# Controller.net
KiCad netlist of a schematic drawn in EAGLE
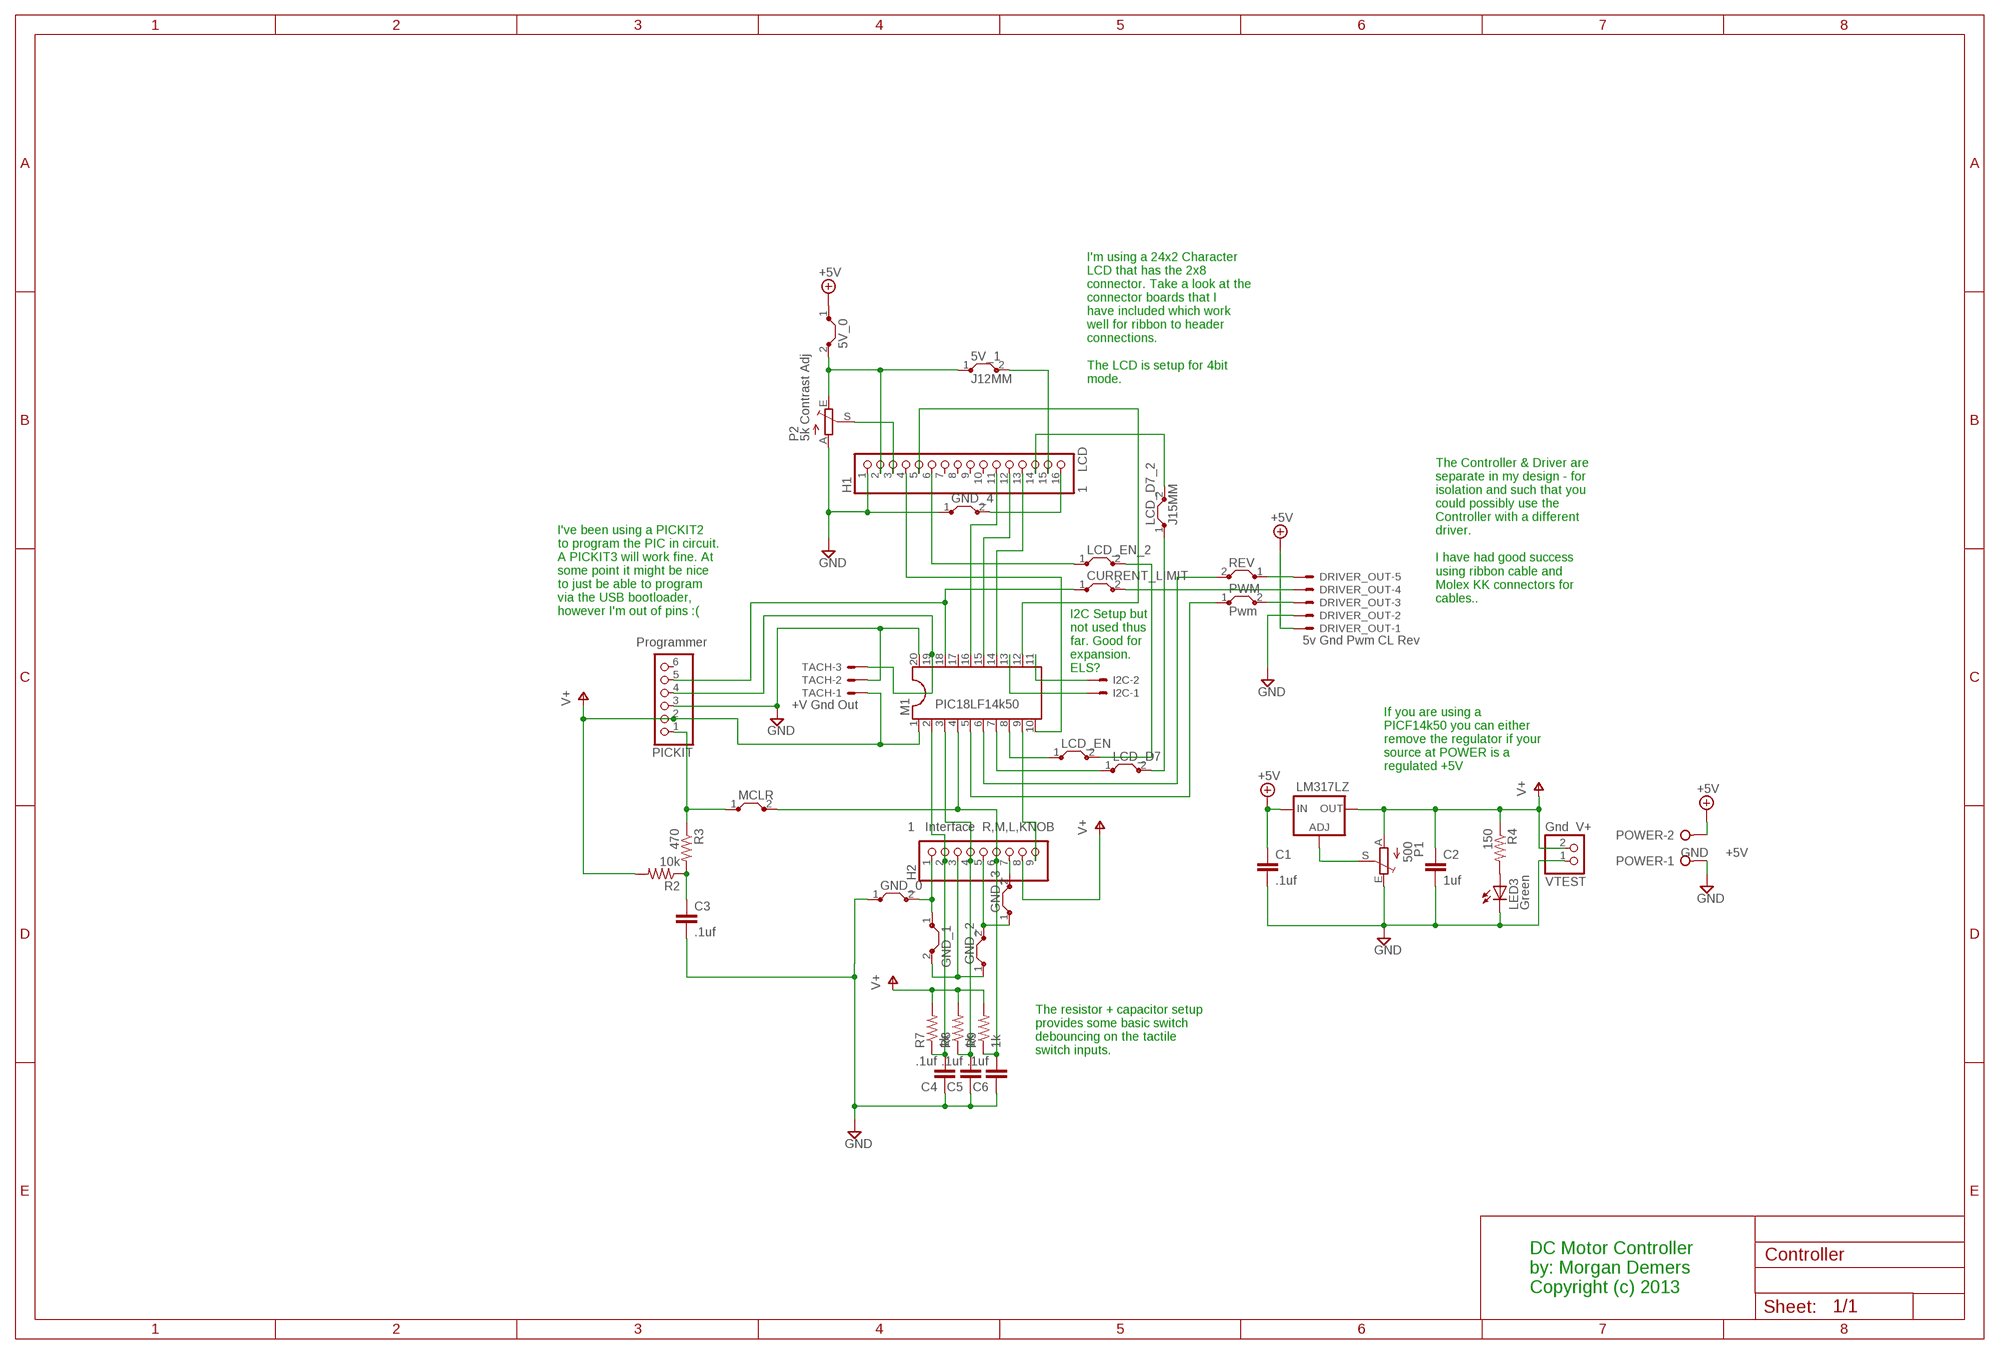
[diagram p0: schematic, sheet 1]

(export (version "E")
  (design (tool "Eeschema 10.0.6"))
  (components
    (comp (ref "5V_0")
      (value "J5MM")
      (footprint "eagle-import:05")
      (libsource (lib "eagle-import") (part "J5MM"))
    )
    (comp (ref "5V_1")
      (value "J12MM")
      (footprint "eagle-import:12")
      (libsource (lib "eagle-import") (part "J12MM"))
    )
    (comp (ref "C1")
      (value ".1uf")
      (footprint "eagle-import:C2.5-3")
      (libsource (lib "eagle-import") (part "C2,5-3"))
    )
    (comp (ref "C2")
      (value "1uf")
      (footprint "eagle-import:C2.5-3")
      (libsource (lib "eagle-import") (part "C2,5-3"))
    )
    (comp (ref "C3")
      (value ".1uf")
      (footprint "eagle-import:C2.5-3")
      (libsource (lib "eagle-import") (part "C2,5-3"))
    )
    (comp (ref "C4")
      (value ".1uf")
      (footprint "eagle-import:C5B2.5")
      (libsource (lib "eagle-import") (part "C5/2.5"))
    )
    (comp (ref "C5")
      (value ".1uf")
      (footprint "eagle-import:C5B2.5")
      (libsource (lib "eagle-import") (part "C5/2.5"))
    )
    (comp (ref "C6")
      (value ".1uf")
      (footprint "eagle-import:C5B2.5")
      (libsource (lib "eagle-import") (part "C5/2.5"))
    )
    (comp (ref "CURRENT_LIMIT")
      (value "J30MM")
      (footprint "eagle-import:30")
      (libsource (lib "eagle-import") (part "J30MM"))
    )
    (comp (ref "DRIVER_OUT")
      (value "5v Gnd Pwm CL Rev")
      (footprint "eagle-import:22-23-2051")
      (fields (field (name "MF") "MOLEX") (field (name "MPN") "22-23-2051"))
      (libsource (lib "eagle-import") (part "22-23-2051"))
    )
    (comp (ref "GND_0")
      (value "J10MM")
      (footprint "eagle-import:10")
      (libsource (lib "eagle-import") (part "J10MM"))
    )
    (comp (ref "GND_1")
      (value "J5MM")
      (footprint "eagle-import:05")
      (libsource (lib "eagle-import") (part "J5MM"))
    )
    (comp (ref "GND_2")
      (value "J5MM")
      (footprint "eagle-import:05")
      (libsource (lib "eagle-import") (part "J5MM"))
    )
    (comp (ref "GND_3")
      (value "J5MM")
      (footprint "eagle-import:05")
      (libsource (lib "eagle-import") (part "J5MM"))
    )
    (comp (ref "GND_4")
      (value "J10MM")
      (footprint "eagle-import:10")
      (libsource (lib "eagle-import") (part "J10MM"))
    )
    (comp (ref "H1")
      (value "1 LCD")
      (footprint "eagle-import:1X16")
      (libsource (lib "eagle-import") (part "PINHD-1X16"))
    )
    (comp (ref "H2")
      (value "1 Interface R,M,L,KNOB")
      (footprint "eagle-import:1X09")
      (libsource (lib "eagle-import") (part "PINHD-1X9"))
    )
    (comp (ref "I2C")
      (value "22-23-2021")
      (footprint "eagle-import:22-23-2021")
      (fields (field (name "MF") "MOLEX"))
      (libsource (lib "eagle-import") (part "22-23-2021"))
    )
    (comp (ref "LCD_D7")
      (value "J7MM")
      (footprint "eagle-import:07")
      (libsource (lib "eagle-import") (part "J7MM"))
    )
    (comp (ref "LCD_D7_2")
      (value "J15MM")
      (footprint "eagle-import:15")
      (libsource (lib "eagle-import") (part "J15MM"))
    )
    (comp (ref "LCD_EN")
      (value "J7MM")
      (footprint "eagle-import:07")
      (libsource (lib "eagle-import") (part "J7MM"))
    )
    (comp (ref "LCD_EN_2")
      (value "J7MM")
      (footprint "eagle-import:07")
      (libsource (lib "eagle-import") (part "J7MM"))
    )
    (comp (ref "LED3")
      (value "Green")
      (footprint "eagle-import:LSU260")
      (libsource (lib "eagle-import") (part "LEDLSU260"))
    )
    (comp (ref "LM317LZ")
      (value "LM317L")
      (footprint "eagle-import:317L")
      (libsource (lib "eagle-import") (part "LM317L"))
    )
    (comp (ref "M1")
      (value "PIC18LF14k50")
      (footprint "eagle-import:DIL20")
      (libsource (lib "eagle-import") (part "DIL20"))
    )
    (comp (ref "MCLR")
      (value "J15MM")
      (footprint "eagle-import:15")
      (libsource (lib "eagle-import") (part "J15MM"))
    )
    (comp (ref "P1")
      (value "500")
      (footprint "eagle-import:B25P")
      (libsource (lib "eagle-import") (part "TRIM_EU-B25P"))
    )
    (comp (ref "P2")
      (value "5k Contrast Adj")
      (footprint "eagle-import:B25P")
      (libsource (lib "eagle-import") (part "TRIM_EU-B25P"))
    )
    (comp (ref "PICKIT")
      (value "Programmer")
      (footprint "eagle-import:1X06_90")
      (libsource (lib "eagle-import") (part "PINHD-1X6/90"))
    )
    (comp (ref "POWER")
      (value "GND +5V")
      (footprint "eagle-import:W237-132")
      (libsource (lib "eagle-import") (part "W237-02P"))
    )
    (comp (ref "PWM")
      (value "Pwm")
      (footprint "eagle-import:07")
      (libsource (lib "eagle-import") (part "J7MM"))
    )
    (comp (ref "R2")
      (value "10k")
      (footprint "eagle-import:0204V")
      (libsource (lib "eagle-import") (part "R-US_0204/2V"))
    )
    (comp (ref "R3")
      (value "470")
      (footprint "eagle-import:0204V")
      (libsource (lib "eagle-import") (part "R-US_0204/2V"))
    )
    (comp (ref "R4")
      (value "150")
      (footprint "eagle-import:0204V")
      (libsource (lib "eagle-import") (part "R-US_0204/2V"))
    )
    (comp (ref "R7")
      (value "1k")
      (footprint "eagle-import:0204V")
      (libsource (lib "eagle-import") (part "R-US_0204/2V"))
    )
    (comp (ref "R8")
      (value "1k")
      (footprint "eagle-import:0204V")
      (libsource (lib "eagle-import") (part "R-US_0204/2V"))
    )
    (comp (ref "R9")
      (value "1k")
      (footprint "eagle-import:0204V")
      (libsource (lib "eagle-import") (part "R-US_0204/2V"))
    )
    (comp (ref "REV")
      (value "J10MM")
      (footprint "eagle-import:10")
      (libsource (lib "eagle-import") (part "J10MM"))
    )
    (comp (ref "TACH")
      (value "+V Gnd Out")
      (footprint "eagle-import:22-23-2031")
      (fields (field (name "MF") "MOLEX") (field (name "MPN") "22-23-2031"))
      (libsource (lib "eagle-import") (part "22-23-2031"))
    )
    (comp (ref "VTEST")
      (value "Gnd V+")
      (footprint "eagle-import:1X02")
      (libsource (lib "eagle-import") (part "PINHD-1X2"))
    )
  )
  (nets
    (net (code "1") (name "+5V") (class "Default")
      (node (ref "5V_0") (pin "1") (pinfunction "1_1") (pintype "passive"))
      (node (ref "C1") (pin "1") (pinfunction "1_1") (pintype "passive"))
      (node (ref "DRIVER_OUT") (pin "1") (pinfunction "S_1") (pintype "passive"))
      (node (ref "LM317LZ") (pin "3") (pinfunction "IN_3") (pintype "input"))
      (node (ref "POWER") (pin "2") (pinfunction "KL_2") (pintype "passive"))
    )
    (net (code "2") (name "GND") (class "Default")
      (node (ref "C1") (pin "2") (pinfunction "2_2") (pintype "passive"))
      (node (ref "C2") (pin "2") (pinfunction "2_2") (pintype "passive"))
      (node (ref "C3") (pin "2") (pinfunction "2_2") (pintype "passive"))
      (node (ref "C4") (pin "1") (pinfunction "1_1") (pintype "passive"))
      (node (ref "C5") (pin "1") (pinfunction "1_1") (pintype "passive"))
      (node (ref "C6") (pin "1") (pinfunction "1_1") (pintype "passive"))
      (node (ref "DRIVER_OUT") (pin "2") (pinfunction "S_2") (pintype "passive"))
      (node (ref "GND_0") (pin "1") (pinfunction "1_1") (pintype "passive"))
      (node (ref "GND_4") (pin "1") (pinfunction "1_1") (pintype "passive"))
      (node (ref "H1") (pin "1") (pinfunction "1_1") (pintype "passive"))
      (node (ref "LED3") (pin "K") (pinfunction "C_K") (pintype "passive"))
      (node (ref "M1") (pin "20") (pinfunction "20_20") (pintype "passive"))
      (node (ref "P1") (pin "E") (pinfunction "E_E") (pintype "passive"))
      (node (ref "P2") (pin "A") (pinfunction "A_A") (pintype "passive"))
      (node (ref "PICKIT") (pin "3") (pinfunction "3_3") (pintype "passive"))
      (node (ref "POWER") (pin "1") (pinfunction "KL_1") (pintype "passive"))
      (node (ref "TACH") (pin "2") (pinfunction "S_2") (pintype "passive"))
      (node (ref "VTEST") (pin "1") (pinfunction "1_1") (pintype "passive"))
    )
    (net (code "3") (name "Net-(5V_0-Pad2)") (class "Default")
      (node (ref "5V_0") (pin "2") (pinfunction "2_2") (pintype "passive"))
      (node (ref "5V_1") (pin "1") (pinfunction "1_1") (pintype "passive"))
      (node (ref "H1") (pin "2") (pinfunction "2_2") (pintype "passive"))
      (node (ref "P2") (pin "E") (pinfunction "E_E") (pintype "passive"))
    )
    (net (code "4") (name "Net-(5V_1-Pad2)") (class "Default")
      (node (ref "5V_1") (pin "2") (pinfunction "2_2") (pintype "passive"))
      (node (ref "H1") (pin "15") (pinfunction "15_15") (pintype "passive"))
    )
    (net (code "5") (name "Net-(C3-Pad1)") (class "Default")
      (node (ref "C3") (pin "1") (pinfunction "1_1") (pintype "passive"))
      (node (ref "R2") (pin "1") (pinfunction "1_1") (pintype "passive"))
      (node (ref "R3") (pin "2") (pinfunction "2_2") (pintype "passive"))
    )
    (net (code "6") (name "Net-(C4-Pad2)") (class "Default")
      (node (ref "C4") (pin "2") (pinfunction "2_2") (pintype "passive"))
      (node (ref "H2") (pin "2") (pinfunction "2_2") (pintype "passive"))
      (node (ref "M1") (pin "2") (pinfunction "2_2") (pintype "passive"))
      (node (ref "R7") (pin "1") (pinfunction "1_1") (pintype "passive"))
    )
    (net (code "7") (name "Net-(C5-Pad2)") (class "Default")
      (node (ref "C5") (pin "2") (pinfunction "2_2") (pintype "passive"))
      (node (ref "H2") (pin "4") (pinfunction "4_4") (pintype "passive"))
      (node (ref "M1") (pin "3") (pinfunction "3_3") (pintype "passive"))
      (node (ref "R8") (pin "1") (pinfunction "1_1") (pintype "passive"))
    )
    (net (code "8") (name "Net-(C6-Pad2)") (class "Default")
      (node (ref "C6") (pin "2") (pinfunction "2_2") (pintype "passive"))
      (node (ref "H2") (pin "6") (pinfunction "6_6") (pintype "passive"))
      (node (ref "M1") (pin "4") (pinfunction "4_4") (pintype "passive"))
      (node (ref "MCLR") (pin "2") (pinfunction "2_2") (pintype "passive"))
      (node (ref "R9") (pin "1") (pinfunction "1_1") (pintype "passive"))
    )
    (net (code "9") (name "Net-(CURRENT_LIMIT-Pad1)") (class "Default")
      (node (ref "CURRENT_LIMIT") (pin "1") (pinfunction "1_1") (pintype "passive"))
      (node (ref "M1") (pin "18") (pinfunction "18_18") (pintype "passive"))
      (node (ref "PICKIT") (pin "5") (pinfunction "5_5") (pintype "passive"))
    )
    (net (code "10") (name "Net-(DRIVER_OUTC-S)") (class "Default")
      (node (ref "DRIVER_OUT") (pin "3") (pinfunction "S_3") (pintype "passive"))
      (node (ref "PWM") (pin "2") (pinfunction "2_2") (pintype "passive"))
    )
    (net (code "11") (name "Net-(DRIVER_OUTD-S)") (class "Default")
      (node (ref "CURRENT_LIMIT") (pin "2") (pinfunction "2_2") (pintype "passive"))
      (node (ref "DRIVER_OUT") (pin "4") (pinfunction "S_4") (pintype "passive"))
    )
    (net (code "12") (name "Net-(DRIVER_OUTE-S)") (class "Default")
      (node (ref "DRIVER_OUT") (pin "5") (pinfunction "S_5") (pintype "passive"))
      (node (ref "REV") (pin "1") (pinfunction "1_1") (pintype "passive"))
    )
    (net (code "13") (name "Net-(GND_0-Pad2)") (class "Default")
      (node (ref "GND_0") (pin "2") (pinfunction "2_2") (pintype "passive"))
      (node (ref "GND_1") (pin "1") (pinfunction "1_1") (pintype "passive"))
      (node (ref "H2") (pin "1") (pinfunction "1_1") (pintype "passive"))
    )
    (net (code "14") (name "Net-(GND_1-Pad2)") (class "Default")
      (node (ref "GND_1") (pin "2") (pinfunction "2_2") (pintype "passive"))
      (node (ref "GND_2") (pin "1") (pinfunction "1_1") (pintype "passive"))
      (node (ref "H2") (pin "3") (pinfunction "3_3") (pintype "passive"))
    )
    (net (code "15") (name "Net-(GND_2-Pad2)") (class "Default")
      (node (ref "GND_2") (pin "2") (pinfunction "2_2") (pintype "passive"))
      (node (ref "GND_3") (pin "1") (pinfunction "1_1") (pintype "passive"))
      (node (ref "H2") (pin "5") (pinfunction "5_5") (pintype "passive"))
    )
    (net (code "16") (name "Net-(GND_3-Pad2)") (class "Default")
      (node (ref "GND_3") (pin "2") (pinfunction "2_2") (pintype "passive"))
      (node (ref "H2") (pin "7") (pinfunction "7_7") (pintype "passive"))
    )
    (net (code "17") (name "Net-(GND_4-Pad2)") (class "Default")
      (node (ref "GND_4") (pin "2") (pinfunction "2_2") (pintype "passive"))
      (node (ref "H1") (pin "16") (pinfunction "16_16") (pintype "passive"))
    )
    (net (code "18") (name "Net-(H1-Pad3)") (class "Default")
      (node (ref "H1") (pin "3") (pinfunction "3_3") (pintype "passive"))
      (node (ref "P2") (pin "S") (pinfunction "S_S") (pintype "passive"))
    )
    (net (code "19") (name "Net-(H1-Pad4)") (class "Default")
      (node (ref "H1") (pin "4") (pinfunction "4_4") (pintype "passive"))
      (node (ref "M1") (pin "10") (pinfunction "10_10") (pintype "passive"))
    )
    (net (code "20") (name "Net-(H1-Pad5)") (class "Default")
      (node (ref "H1") (pin "5") (pinfunction "5_5") (pintype "passive"))
      (node (ref "M1") (pin "12") (pinfunction "12_12") (pintype "passive"))
    )
    (net (code "21") (name "Net-(H1-Pad6)") (class "Default")
      (node (ref "H1") (pin "6") (pinfunction "6_6") (pintype "passive"))
      (node (ref "LCD_EN_2") (pin "1") (pinfunction "1_1") (pintype "passive"))
    )
    (net (code "22") (name "Net-(H1-Pad11)") (class "Default")
      (node (ref "H1") (pin "11") (pinfunction "11_11") (pintype "passive"))
      (node (ref "M1") (pin "16") (pinfunction "16_16") (pintype "passive"))
    )
    (net (code "23") (name "Net-(H1-Pad12)") (class "Default")
      (node (ref "H1") (pin "12") (pinfunction "12_12") (pintype "passive"))
      (node (ref "M1") (pin "15") (pinfunction "15_15") (pintype "passive"))
    )
    (net (code "24") (name "Net-(H1-Pad13)") (class "Default")
      (node (ref "H1") (pin "13") (pinfunction "13_13") (pintype "passive"))
      (node (ref "M1") (pin "14") (pinfunction "14_14") (pintype "passive"))
    )
    (net (code "25") (name "Net-(H1-Pad14)") (class "Default")
      (node (ref "H1") (pin "14") (pinfunction "14_14") (pintype "passive"))
      (node (ref "LCD_D7_2") (pin "2") (pinfunction "2_2") (pintype "passive"))
    )
    (net (code "26") (name "Net-(H2-Pad9)") (class "Default")
      (node (ref "H2") (pin "9") (pinfunction "9_9") (pintype "passive"))
      (node (ref "M1") (pin "9") (pinfunction "9_9") (pintype "passive"))
    )
    (net (code "27") (name "Net-(I2CA-S)") (class "Default")
      (node (ref "I2C") (pin "1") (pinfunction "S_1") (pintype "passive"))
      (node (ref "M1") (pin "13") (pinfunction "13_13") (pintype "passive"))
    )
    (net (code "28") (name "Net-(I2CB-S)") (class "Default")
      (node (ref "I2C") (pin "2") (pinfunction "S_2") (pintype "passive"))
      (node (ref "M1") (pin "11") (pinfunction "11_11") (pintype "passive"))
    )
    (net (code "29") (name "Net-(LCD_D7-Pad1)") (class "Default")
      (node (ref "LCD_D7") (pin "1") (pinfunction "1_1") (pintype "passive"))
      (node (ref "M1") (pin "7") (pinfunction "7_7") (pintype "passive"))
    )
    (net (code "30") (name "Net-(LCD_D7-Pad2)") (class "Default")
      (node (ref "LCD_D7") (pin "2") (pinfunction "2_2") (pintype "passive"))
      (node (ref "LCD_D7_2") (pin "1") (pinfunction "1_1") (pintype "passive"))
    )
    (net (code "31") (name "Net-(LCD_EN-Pad1)") (class "Default")
      (node (ref "LCD_EN") (pin "1") (pinfunction "1_1") (pintype "passive"))
      (node (ref "M1") (pin "8") (pinfunction "8_8") (pintype "passive"))
    )
    (net (code "32") (name "Net-(LCD_EN-Pad2)") (class "Default")
      (node (ref "LCD_EN") (pin "2") (pinfunction "2_2") (pintype "passive"))
      (node (ref "LCD_EN_2") (pin "2") (pinfunction "2_2") (pintype "passive"))
    )
    (net (code "33") (name "Net-(LED3-PadA)") (class "Default")
      (node (ref "LED3") (pin "A") (pinfunction "A_A") (pintype "passive"))
      (node (ref "R4") (pin "2") (pinfunction "2_2") (pintype "passive"))
    )
    (net (code "34") (name "Net-(LM317LZ-ADJ)") (class "Default")
      (node (ref "LM317LZ") (pin "1") (pinfunction "ADJ_1") (pintype "input"))
      (node (ref "P1") (pin "S") (pinfunction "S_S") (pintype "passive"))
    )
    (net (code "35") (name "Net-(M1-Pad5)") (class "Default")
      (node (ref "M1") (pin "5") (pinfunction "5_5") (pintype "passive"))
      (node (ref "PWM") (pin "1") (pinfunction "1_1") (pintype "passive"))
    )
    (net (code "36") (name "Net-(M1-Pad6)") (class "Default")
      (node (ref "M1") (pin "6") (pinfunction "6_6") (pintype "passive"))
      (node (ref "REV") (pin "2") (pinfunction "2_2") (pintype "passive"))
    )
    (net (code "37") (name "Net-(MCLR-Pad1)") (class "Default")
      (node (ref "MCLR") (pin "1") (pinfunction "1_1") (pintype "passive"))
      (node (ref "PICKIT") (pin "1") (pinfunction "1_1") (pintype "passive"))
      (node (ref "R3") (pin "1") (pinfunction "1_1") (pintype "passive"))
    )
    (net (code "38") (name "Net-(TACHC-S)") (class "Default")
      (node (ref "M1") (pin "19") (pinfunction "19_19") (pintype "passive"))
      (node (ref "PICKIT") (pin "4") (pinfunction "4_4") (pintype "passive"))
      (node (ref "TACH") (pin "3") (pinfunction "S_3") (pintype "passive"))
    )
    (net (code "39") (name "V+") (class "Default")
      (node (ref "C2") (pin "1") (pinfunction "1_1") (pintype "passive"))
      (node (ref "H2") (pin "8") (pinfunction "8_8") (pintype "passive"))
      (node (ref "LM317LZ") (pin "2") (pinfunction "OUT_2") (pintype "passive"))
      (node (ref "M1") (pin "1") (pinfunction "1_1") (pintype "passive"))
      (node (ref "P1") (pin "A") (pinfunction "A_A") (pintype "passive"))
      (node (ref "PICKIT") (pin "2") (pinfunction "2_2") (pintype "passive"))
      (node (ref "R2") (pin "2") (pinfunction "2_2") (pintype "passive"))
      (node (ref "R4") (pin "1") (pinfunction "1_1") (pintype "passive"))
      (node (ref "R7") (pin "2") (pinfunction "2_2") (pintype "passive"))
      (node (ref "R8") (pin "2") (pinfunction "2_2") (pintype "passive"))
      (node (ref "R9") (pin "2") (pinfunction "2_2") (pintype "passive"))
      (node (ref "TACH") (pin "1") (pinfunction "S_1") (pintype "passive"))
      (node (ref "VTEST") (pin "2") (pinfunction "2_2") (pintype "passive"))
    )
    (net (code "40") (name "unconnected-(H1-Pad7)") (class "Default")
      (node (ref "H1") (pin "7") (pinfunction "7_7") (pintype "passive"))
    )
    (net (code "41") (name "unconnected-(H1-Pad8)") (class "Default")
      (node (ref "H1") (pin "8") (pinfunction "8_8") (pintype "passive"))
    )
    (net (code "42") (name "unconnected-(H1-Pad9)") (class "Default")
      (node (ref "H1") (pin "9") (pinfunction "9_9") (pintype "passive"))
    )
    (net (code "43") (name "unconnected-(H1-Pad10)") (class "Default")
      (node (ref "H1") (pin "10") (pinfunction "10_10") (pintype "passive"))
    )
    (net (code "44") (name "unconnected-(M1-Pad17)") (class "Default")
      (node (ref "M1") (pin "17") (pinfunction "17_17") (pintype "passive"))
    )
    (net (code "45") (name "unconnected-(PICKIT-Pad6)") (class "Default")
      (node (ref "PICKIT") (pin "6") (pinfunction "6_6") (pintype "passive"))
    )
  )
)
